# stair_light_psu.net
KiCad netlist of a schematic drawn in EAGLE
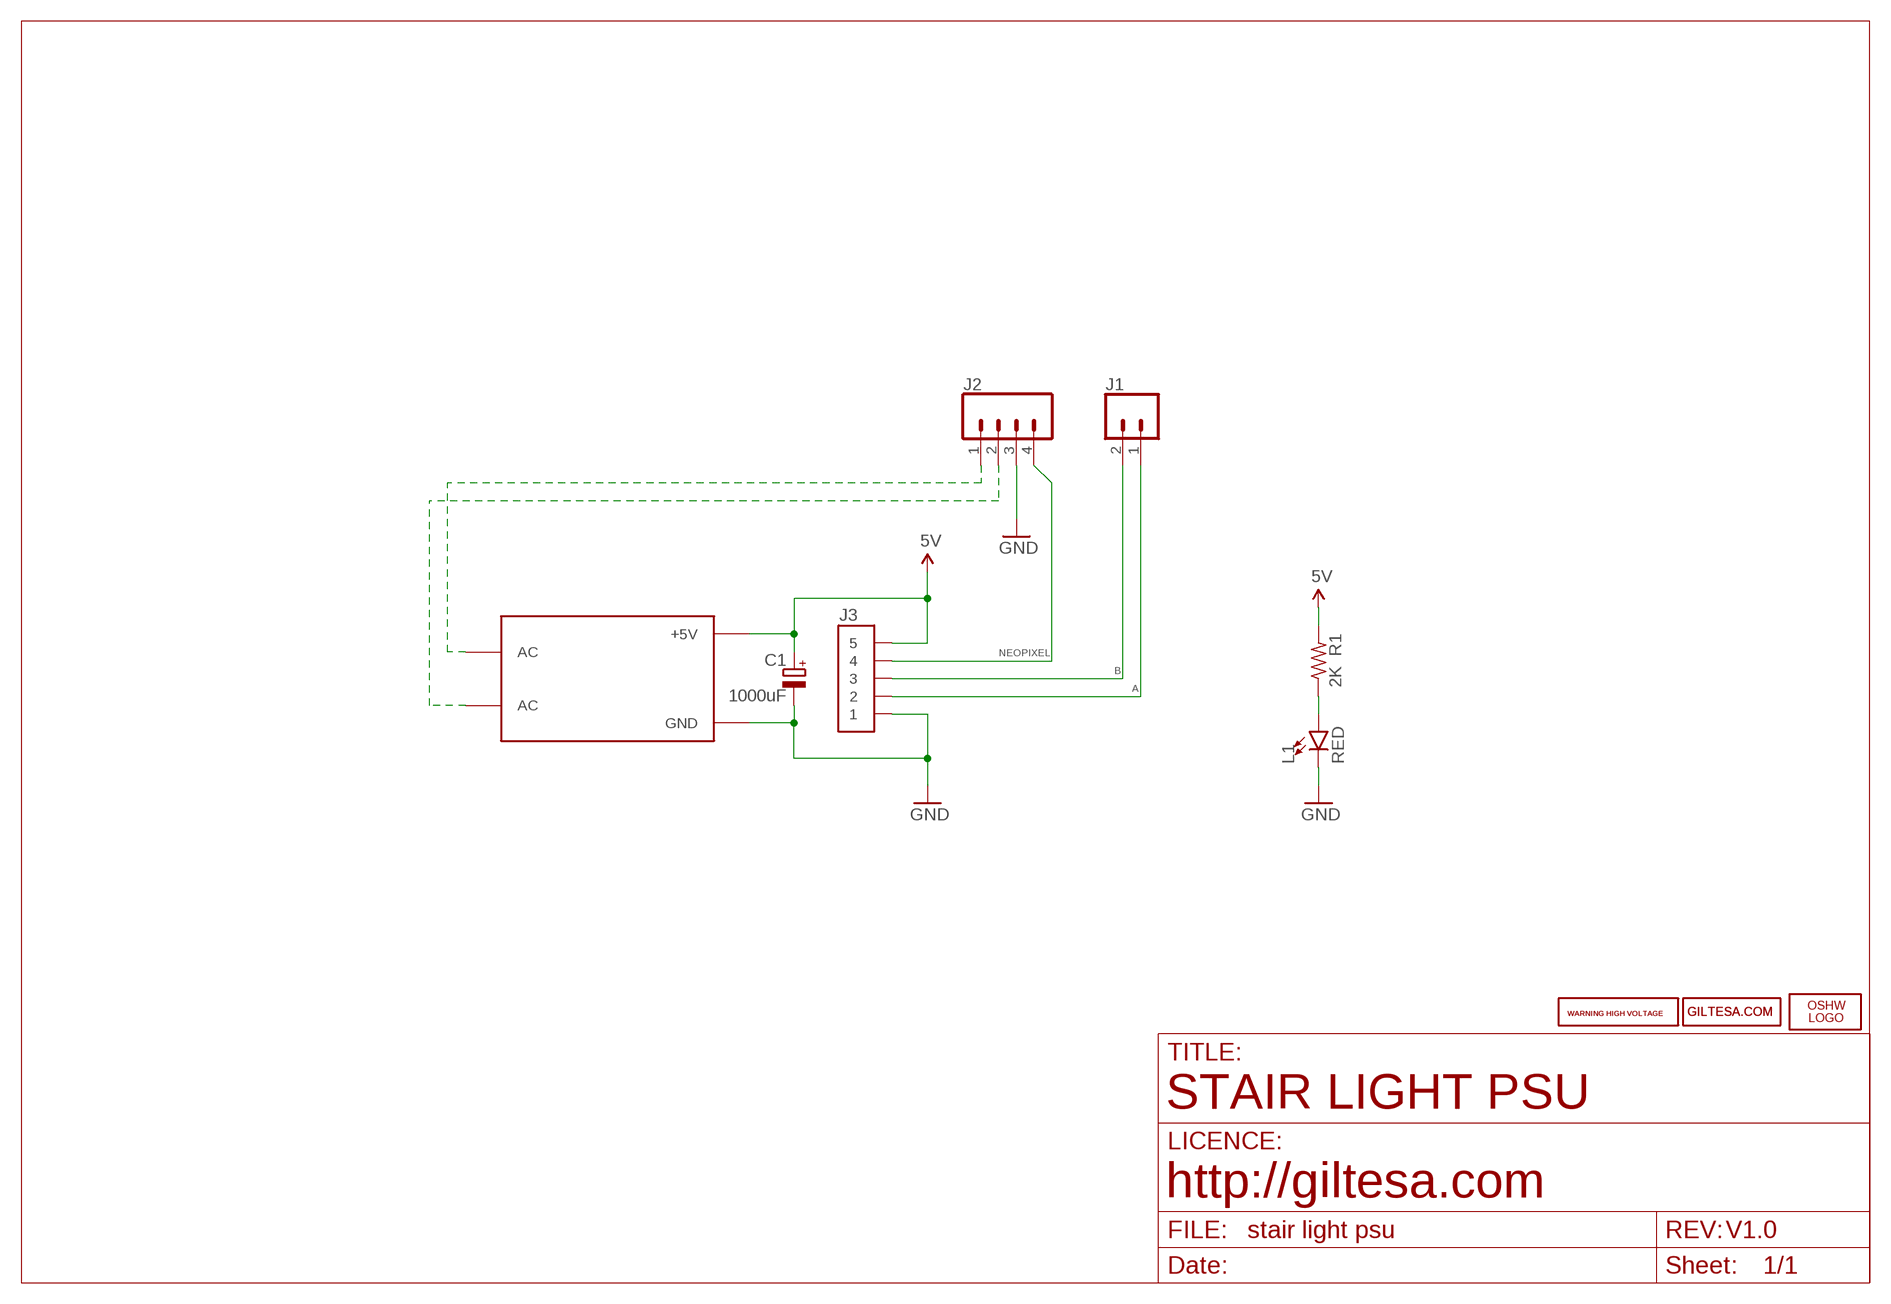
[diagram p0: schematic, sheet 1]

(export (version "E")
  (design (tool "Eeschema 10.0.6"))
  (components
    (comp (ref "C1")
      (value "1000uF")
      (footprint "eagle-import:B45181A")
      (libsource (lib "eagle-import") (part "CPOL-EUB45181A"))
    )
    (comp (ref "J1")
      (value "TERMINAL_5MM_2P1")
      (footprint "eagle-import:TERMINAL_5MM_2P")
      (libsource (lib "eagle-import") (part "TERMINAL_5MM_2P1"))
    )
    (comp (ref "J2")
      (value "TERMINAL_5MM_4P_90º_20A")
      (footprint "eagle-import:TERMINAL_5MM_4P_90º_20A")
      (libsource (lib "eagle-import") (part "TERMINAL_5MM_4P_90º_20A"))
    )
    (comp (ref "J3")
      (value "1X05")
      (footprint "eagle-import:1X5_SMT_2MM")
      (libsource (lib "eagle-import") (part "1X05"))
    )
    (comp (ref "L1")
      (value "RED")
      (footprint "eagle-import:LED-0603")
      (libsource (lib "eagle-import") (part "LED-BLUE0603"))
    )
    (comp (ref "LOGO1")
      (value "OSHW_LOGO_FILLX0150-NT")
      (footprint "eagle-import:OSHW_FILLX150_NOTEXT")
      (libsource (lib "eagle-import") (part "OSHW_LOGO_FILLX0150-NT"))
    )
    (comp (ref "R1")
      (value "2K")
      (footprint "eagle-import:R0603")
      (libsource (lib "eagle-import") (part "R0603"))
    )
    (comp (ref "U$3")
      (value "WARNING_HIGH_VOLTAGE1")
      (footprint "eagle-import:WARNING_HIGH_VOLTAGE")
      (libsource (lib "eagle-import") (part "WARNING_HIGH_VOLTAGE1"))
    )
    (comp (ref "U$6")
      (value "WARNING_HIGH_VOLTAGE1")
      (footprint "eagle-import:WARNING_HIGH_VOLTAGE")
      (libsource (lib "eagle-import") (part "WARNING_HIGH_VOLTAGE1"))
    )
    (comp (ref "U$10")
      (value "GILTESA.COM_COPPER")
      (footprint "eagle-import:GILTESA.COM_COPPER")
      (libsource (lib "eagle-import") (part "GILTESA.COM_COPPER"))
    )
    (comp (ref "U$13")
      (value "GILTESA.COM_MASK")
      (footprint "eagle-import:GILTESA.COM_MASK")
      (libsource (lib "eagle-import") (part "GILTESA.COM_MASK"))
    )
    (comp (ref "U1")
      (value "HILINK HLK-PM01 5V")
      (footprint "eagle-import:HILINK_HLK-PM01_5V")
      (libsource (lib "eagle-import") (part "HILINK_HLK-PM01_5V"))
    )
  )
  (nets
    (net (code "1") (name "/A") (class "Default")
      (node (ref "J1") (pin "1") (pinfunction "1_1") (pintype "passive"))
      (node (ref "J3") (pin "2") (pinfunction "2_2") (pintype "passive"))
    )
    (net (code "2") (name "/B") (class "Default")
      (node (ref "J1") (pin "2") (pinfunction "2_2") (pintype "passive"))
      (node (ref "J3") (pin "3") (pinfunction "3_3") (pintype "passive"))
    )
    (net (code "3") (name "/NEOPIXEL") (class "Default")
      (node (ref "J2") (pin "4") (pinfunction "4_4") (pintype "passive"))
      (node (ref "J3") (pin "4") (pinfunction "4_4") (pintype "passive"))
    )
    (net (code "4") (name "5V") (class "Default")
      (node (ref "C1") (pin "+") (pinfunction "+_+") (pintype "passive"))
      (node (ref "J3") (pin "5") (pinfunction "5_5") (pintype "passive"))
      (node (ref "R1") (pin "2") (pinfunction "2_2") (pintype "passive"))
      (node (ref "U1") (pin "+5V") (pinfunction "+5V_+5V") (pintype "output"))
    )
    (net (code "5") (name "GND") (class "Default")
      (node (ref "C1") (pin "-") (pinfunction "-_-") (pintype "passive"))
      (node (ref "J2") (pin "3") (pinfunction "3_3") (pintype "passive"))
      (node (ref "J3") (pin "1") (pinfunction "1_1") (pintype "passive"))
      (node (ref "L1") (pin "C") (pinfunction "C_C") (pintype "passive"))
      (node (ref "U1") (pin "GND") (pinfunction "GND_GND") (pintype "output"))
    )
    (net (code "6") (name "Net-(J2-Pad1)") (class "Default")
      (node (ref "J2") (pin "1") (pinfunction "1_1") (pintype "passive"))
      (node (ref "U1") (pin "AC@2") (pinfunction "AC_AC@2") (pintype "input"))
    )
    (net (code "7") (name "Net-(J2-Pad2)") (class "Default")
      (node (ref "J2") (pin "2") (pinfunction "2_2") (pintype "passive"))
      (node (ref "U1") (pin "AC@1") (pinfunction "AC_AC@1") (pintype "input"))
    )
    (net (code "8") (name "Net-(L1-PadA)") (class "Default")
      (node (ref "L1") (pin "A") (pinfunction "A_A") (pintype "passive"))
      (node (ref "R1") (pin "1") (pinfunction "1_1") (pintype "passive"))
    )
  )
)
